# MCU.net
KiCad netlist of a schematic drawn in Altium Designer
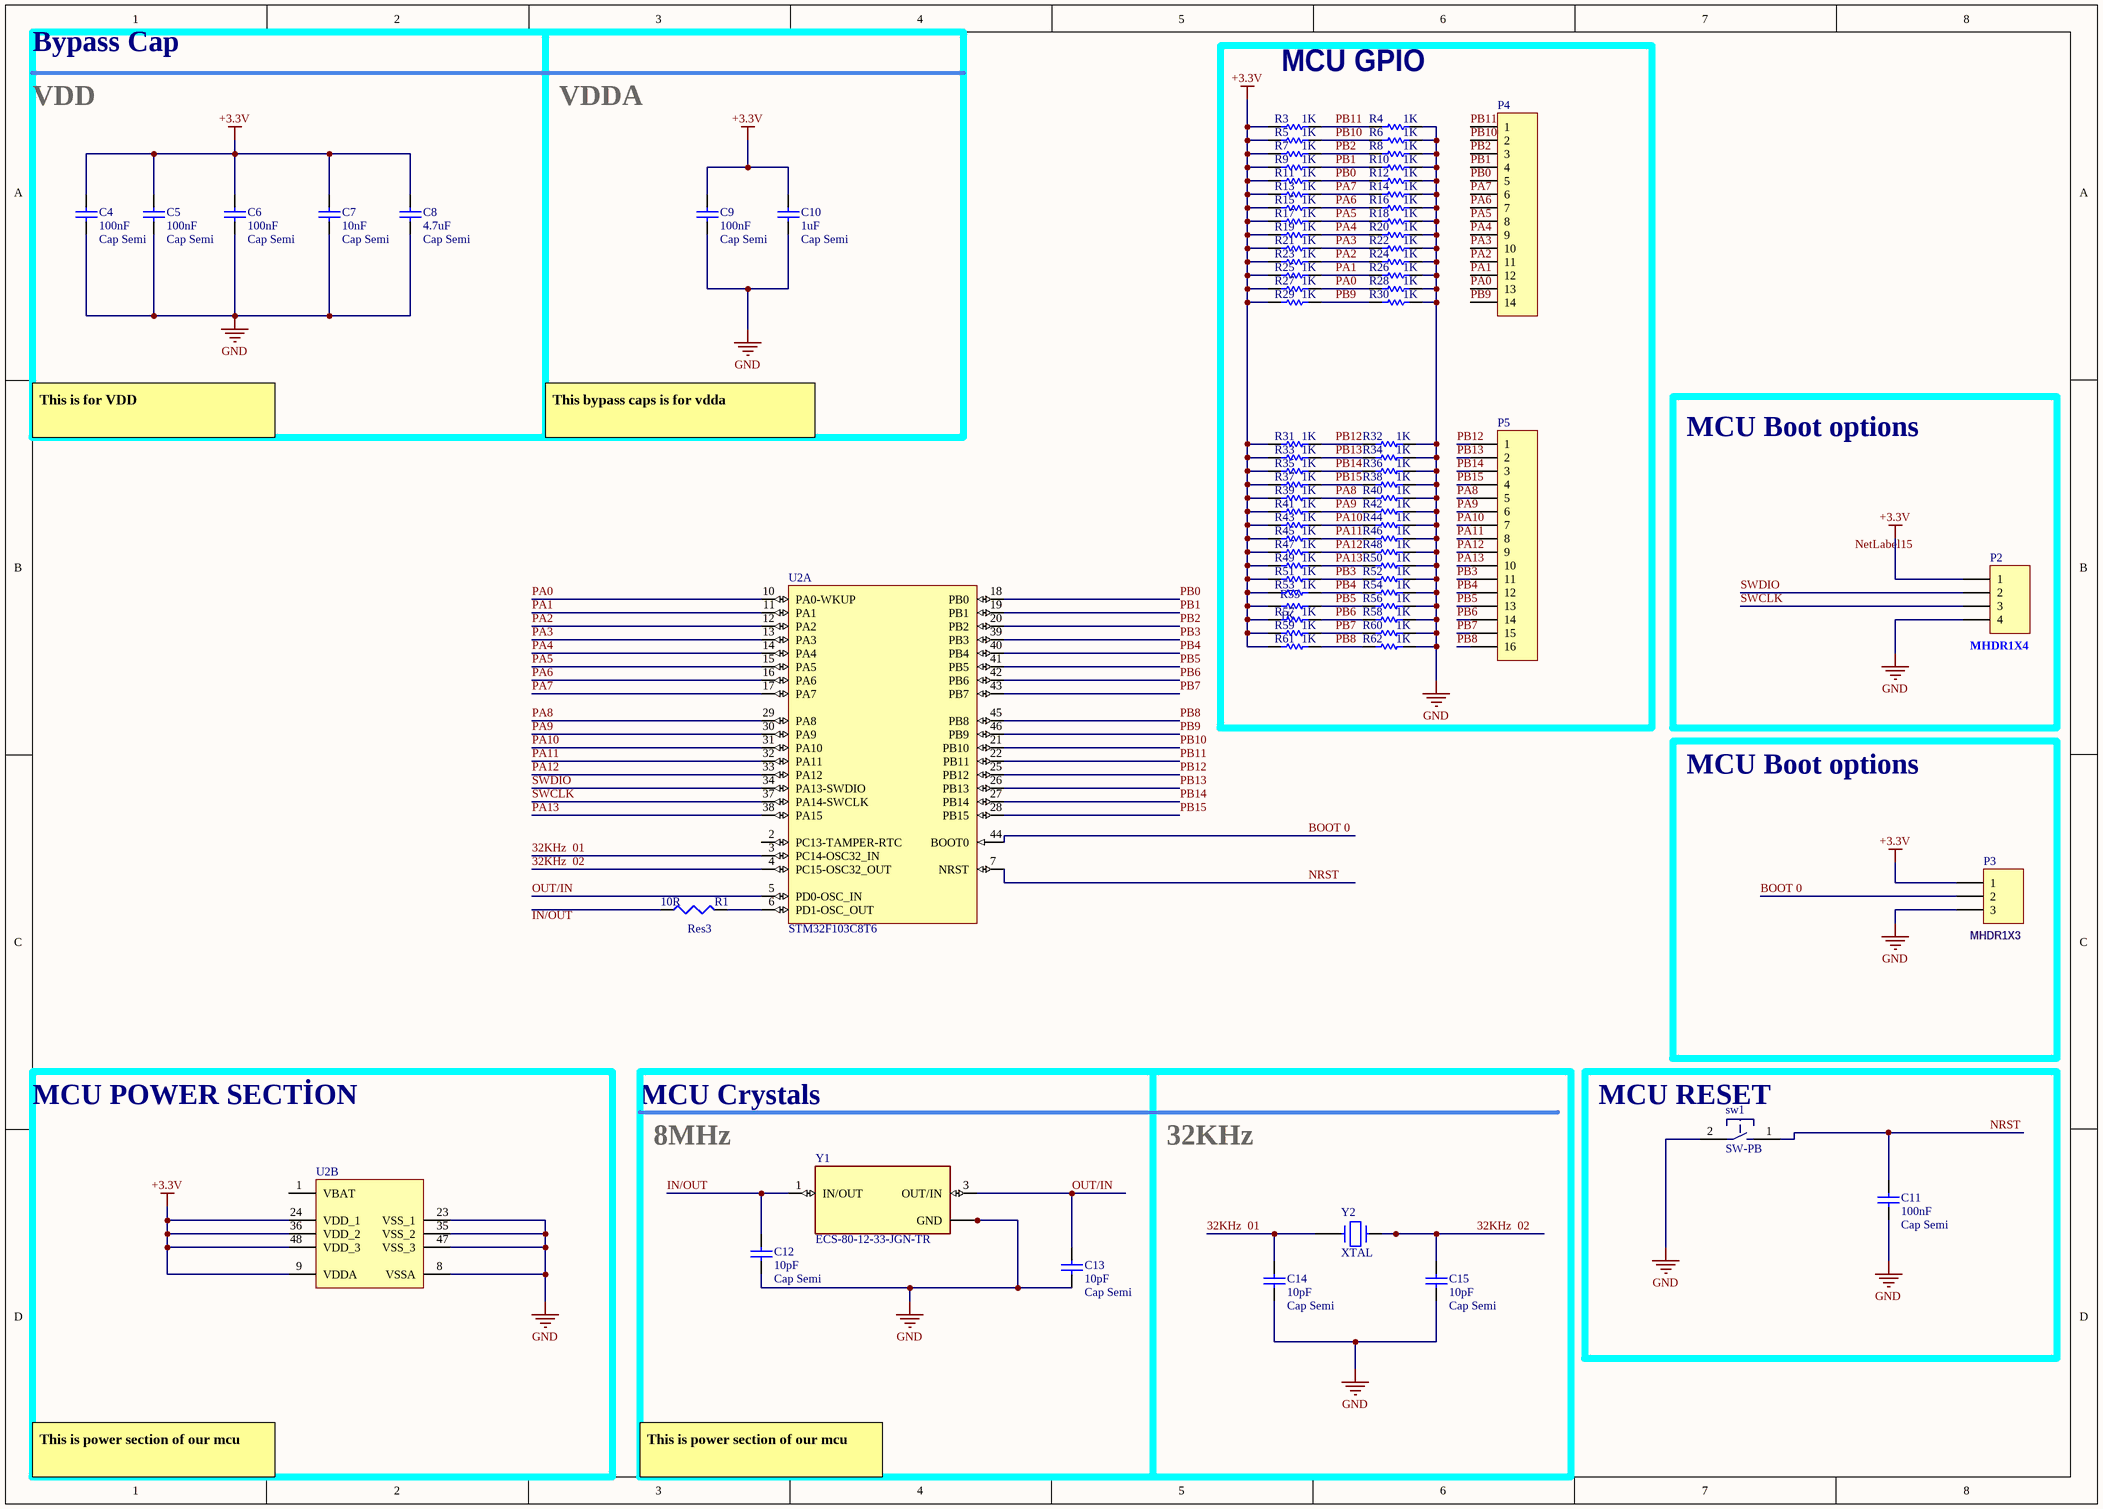
[diagram p0: MCU.SchDoc]

(export (version "E")
  (design (tool "Eeschema 10.0.6"))
  (components
    (comp (ref "C4")
      (value "Cap Semi")
      (footprint "1608[0603]")
      (description "Capacitor (Semiconductor SIM Model)")
      (fields (field (name "ALTIUM_VALUE") "100nF") (field (name "PUBLISHER") "Altium Limited"))
      (libsource (lib "Miscellaneous Devices") (part "Cap Semi"))
    )
    (comp (ref "C5")
      (value "Cap Semi")
      (footprint "1608[0603]")
      (description "Capacitor (Semiconductor SIM Model)")
      (fields (field (name "ALTIUM_VALUE") "100nF") (field (name "PUBLISHER") "Altium Limited"))
      (libsource (lib "Miscellaneous Devices") (part "Cap Semi"))
    )
    (comp (ref "C6")
      (value "Cap Semi")
      (footprint "1608[0603]")
      (description "Capacitor (Semiconductor SIM Model)")
      (fields (field (name "ALTIUM_VALUE") "100nF") (field (name "PUBLISHER") "Altium Limited"))
      (libsource (lib "Miscellaneous Devices") (part "Cap Semi"))
    )
    (comp (ref "C7")
      (value "Cap Semi")
      (footprint "1608[0603]")
      (description "Capacitor (Semiconductor SIM Model)")
      (fields (field (name "ALTIUM_VALUE") "10nF") (field (name "PUBLISHER") "Altium Limited"))
      (libsource (lib "Miscellaneous Devices") (part "Cap Semi"))
    )
    (comp (ref "C8")
      (value "Cap Semi")
      (footprint "1608[0603]")
      (description "Capacitor (Semiconductor SIM Model)")
      (fields (field (name "ALTIUM_VALUE") "4.7uF") (field (name "PUBLISHER") "Altium Limited"))
      (libsource (lib "Miscellaneous Devices") (part "Cap Semi"))
    )
    (comp (ref "C9")
      (value "Cap Semi")
      (footprint "1608[0603]")
      (description "Capacitor (Semiconductor SIM Model)")
      (fields (field (name "ALTIUM_VALUE") "100nF") (field (name "PUBLISHER") "Altium Limited"))
      (libsource (lib "Miscellaneous Devices") (part "Cap Semi"))
    )
    (comp (ref "C10")
      (value "Cap Semi")
      (footprint "1608[0603]")
      (description "Capacitor (Semiconductor SIM Model)")
      (fields (field (name "ALTIUM_VALUE") "1uF") (field (name "PUBLISHER") "Altium Limited"))
      (libsource (lib "Miscellaneous Devices") (part "Cap Semi"))
    )
    (comp (ref "C11")
      (value "Cap Semi")
      (footprint "1608[0603]")
      (description "Capacitor (Semiconductor SIM Model)")
      (fields (field (name "ALTIUM_VALUE") "100nF") (field (name "PUBLISHER") "Altium Limited"))
      (libsource (lib "Miscellaneous Devices") (part "Cap Semi"))
    )
    (comp (ref "C12")
      (value "Cap Semi")
      (footprint "0402")
      (description "Capacitor (Semiconductor SIM Model)")
      (fields (field (name "ALTIUM_VALUE") "10pF") (field (name "PUBLISHER") "Altium Limited"))
      (libsource (lib "Miscellaneous Devices") (part "Cap Semi"))
    )
    (comp (ref "C13")
      (value "Cap Semi")
      (footprint "0402")
      (description "Capacitor (Semiconductor SIM Model)")
      (fields (field (name "ALTIUM_VALUE") "10pF") (field (name "PUBLISHER") "Altium Limited"))
      (libsource (lib "Miscellaneous Devices") (part "Cap Semi"))
    )
    (comp (ref "C14")
      (value "Cap Semi")
      (footprint "0402")
      (description "Capacitor (Semiconductor SIM Model)")
      (fields (field (name "ALTIUM_VALUE") "10pF") (field (name "PUBLISHER") "Altium Limited"))
      (libsource (lib "Miscellaneous Devices") (part "Cap Semi"))
    )
    (comp (ref "C15")
      (value "Cap Semi")
      (footprint "0402")
      (description "Capacitor (Semiconductor SIM Model)")
      (fields (field (name "ALTIUM_VALUE") "10pF") (field (name "PUBLISHER") "Altium Limited"))
      (libsource (lib "Miscellaneous Devices") (part "Cap Semi"))
    )
    (comp (ref "P2")
      (value "Header 4")
      (footprint "MY_MA04-1W")
      (description "Header, 4-Pin")
      (fields (field (name "ASID PART NUMBER") "Header 4-AS"))
      (libsource (lib "Mylib+Rev+4") (part "Header 4"))
    )
    (comp (ref "P3")
      (value "Header 3")
      (footprint "MY_MA03-1W")
      (description "Header, 3-Pin")
      (fields (field (name "ASID PART NUMBER") "Header 3-AS"))
      (libsource (lib "Mylib+Rev+4") (part "Header 3"))
    )
    (comp (ref "P4")
      (value "Header 14")
      (footprint "MY_FE14")
      (description "Header, 14-Pin")
      (fields (field (name "ASID PART NUMBER") "Header 14-AS"))
      (libsource (lib "Mylib+Rev+4") (part "Header 14"))
    )
    (comp (ref "P5")
      (value "Header 16")
      (footprint "MY_FE16")
      (description "Header, 16-Pin")
      (fields (field (name "ASID PART NUMBER") "Header 16-AS"))
      (libsource (lib "Mylib+Rev+4") (part "Header 16"))
    )
    (comp (ref "R1")
      (value "Res3")
      (footprint "J1-0603")
      (description "Resistor")
      (fields (field (name "ALTIUM_VALUE") "10R") (field (name "PUBLISHER") "Altium Limited"))
      (libsource (lib "Miscellaneous Devices") (part "Res3"))
    )
    (comp (ref "R3")
      (value "1K")
      (footprint "MY_0603")
      (description "Standard resistor")
      (fields (field (name "ASID PART NUMBER") "Res-AS"))
      (libsource (lib "Mylib+Rev+4") (part "Res"))
    )
    (comp (ref "R4")
      (value "1K")
      (footprint "MY_0603")
      (description "Standard resistor")
      (fields (field (name "ASID PART NUMBER") "Res-AS"))
      (libsource (lib "Mylib+Rev+4") (part "Res"))
    )
    (comp (ref "R5")
      (value "1K")
      (footprint "MY_0603")
      (description "Standard resistor")
      (fields (field (name "ASID PART NUMBER") "Res-AS"))
      (libsource (lib "Mylib+Rev+4") (part "Res"))
    )
    (comp (ref "R6")
      (value "1K")
      (footprint "MY_0603")
      (description "Standard resistor")
      (fields (field (name "ASID PART NUMBER") "Res-AS"))
      (libsource (lib "Mylib+Rev+4") (part "Res"))
    )
    (comp (ref "R7")
      (value "1K")
      (footprint "MY_0603")
      (description "Standard resistor")
      (fields (field (name "ASID PART NUMBER") "Res-AS"))
      (libsource (lib "Mylib+Rev+4") (part "Res"))
    )
    (comp (ref "R8")
      (value "1K")
      (footprint "MY_0603")
      (description "Standard resistor")
      (fields (field (name "ASID PART NUMBER") "Res-AS"))
      (libsource (lib "Mylib+Rev+4") (part "Res"))
    )
    (comp (ref "R9")
      (value "1K")
      (footprint "MY_0603")
      (description "Standard resistor")
      (fields (field (name "ASID PART NUMBER") "Res-AS"))
      (libsource (lib "Mylib+Rev+4") (part "Res"))
    )
    (comp (ref "R10")
      (value "1K")
      (footprint "MY_0603")
      (description "Standard resistor")
      (fields (field (name "ASID PART NUMBER") "Res-AS"))
      (libsource (lib "Mylib+Rev+4") (part "Res"))
    )
    (comp (ref "R11")
      (value "1K")
      (footprint "MY_0603")
      (description "Standard resistor")
      (fields (field (name "ASID PART NUMBER") "Res-AS"))
      (libsource (lib "Mylib+Rev+4") (part "Res"))
    )
    (comp (ref "R12")
      (value "1K")
      (footprint "MY_0603")
      (description "Standard resistor")
      (fields (field (name "ASID PART NUMBER") "Res-AS"))
      (libsource (lib "Mylib+Rev+4") (part "Res"))
    )
    (comp (ref "R13")
      (value "1K")
      (footprint "MY_0603")
      (description "Standard resistor")
      (fields (field (name "ASID PART NUMBER") "Res-AS"))
      (libsource (lib "Mylib+Rev+4") (part "Res"))
    )
    (comp (ref "R14")
      (value "1K")
      (footprint "MY_0603")
      (description "Standard resistor")
      (fields (field (name "ASID PART NUMBER") "Res-AS"))
      (libsource (lib "Mylib+Rev+4") (part "Res"))
    )
    (comp (ref "R15")
      (value "1K")
      (footprint "MY_0603")
      (description "Standard resistor")
      (fields (field (name "ASID PART NUMBER") "Res-AS"))
      (libsource (lib "Mylib+Rev+4") (part "Res"))
    )
    (comp (ref "R16")
      (value "1K")
      (footprint "MY_0603")
      (description "Standard resistor")
      (fields (field (name "ASID PART NUMBER") "Res-AS"))
      (libsource (lib "Mylib+Rev+4") (part "Res"))
    )
    (comp (ref "R17")
      (value "1K")
      (footprint "MY_0603")
      (description "Standard resistor")
      (fields (field (name "ASID PART NUMBER") "Res-AS"))
      (libsource (lib "Mylib+Rev+4") (part "Res"))
    )
    (comp (ref "R18")
      (value "1K")
      (footprint "MY_0603")
      (description "Standard resistor")
      (fields (field (name "ASID PART NUMBER") "Res-AS"))
      (libsource (lib "Mylib+Rev+4") (part "Res"))
    )
    (comp (ref "R19")
      (value "1K")
      (footprint "MY_0603")
      (description "Standard resistor")
      (fields (field (name "ASID PART NUMBER") "Res-AS"))
      (libsource (lib "Mylib+Rev+4") (part "Res"))
    )
    (comp (ref "R20")
      (value "1K")
      (footprint "MY_0603")
      (description "Standard resistor")
      (fields (field (name "ASID PART NUMBER") "Res-AS"))
      (libsource (lib "Mylib+Rev+4") (part "Res"))
    )
    (comp (ref "R21")
      (value "1K")
      (footprint "MY_0603")
      (description "Standard resistor")
      (fields (field (name "ASID PART NUMBER") "Res-AS"))
      (libsource (lib "Mylib+Rev+4") (part "Res"))
    )
    (comp (ref "R22")
      (value "1K")
      (footprint "MY_0603")
      (description "Standard resistor")
      (fields (field (name "ASID PART NUMBER") "Res-AS"))
      (libsource (lib "Mylib+Rev+4") (part "Res"))
    )
    (comp (ref "R23")
      (value "1K")
      (footprint "MY_0603")
      (description "Standard resistor")
      (fields (field (name "ASID PART NUMBER") "Res-AS"))
      (libsource (lib "Mylib+Rev+4") (part "Res"))
    )
    (comp (ref "R24")
      (value "1K")
      (footprint "MY_0603")
      (description "Standard resistor")
      (fields (field (name "ASID PART NUMBER") "Res-AS"))
      (libsource (lib "Mylib+Rev+4") (part "Res"))
    )
    (comp (ref "R25")
      (value "1K")
      (footprint "MY_0603")
      (description "Standard resistor")
      (fields (field (name "ASID PART NUMBER") "Res-AS"))
      (libsource (lib "Mylib+Rev+4") (part "Res"))
    )
    (comp (ref "R26")
      (value "1K")
      (footprint "MY_0603")
      (description "Standard resistor")
      (fields (field (name "ASID PART NUMBER") "Res-AS"))
      (libsource (lib "Mylib+Rev+4") (part "Res"))
    )
    (comp (ref "R27")
      (value "1K")
      (footprint "MY_0603")
      (description "Standard resistor")
      (fields (field (name "ASID PART NUMBER") "Res-AS"))
      (libsource (lib "Mylib+Rev+4") (part "Res"))
    )
    (comp (ref "R28")
      (value "1K")
      (footprint "MY_0603")
      (description "Standard resistor")
      (fields (field (name "ASID PART NUMBER") "Res-AS"))
      (libsource (lib "Mylib+Rev+4") (part "Res"))
    )
    (comp (ref "R29")
      (value "1K")
      (footprint "MY_0603")
      (description "Standard resistor")
      (fields (field (name "ASID PART NUMBER") "Res-AS"))
      (libsource (lib "Mylib+Rev+4") (part "Res"))
    )
    (comp (ref "R30")
      (value "1K")
      (footprint "MY_0603")
      (description "Standard resistor")
      (fields (field (name "ASID PART NUMBER") "Res-AS"))
      (libsource (lib "Mylib+Rev+4") (part "Res"))
    )
    (comp (ref "R31")
      (value "1K")
      (footprint "MY_0603")
      (description "Standard resistor")
      (fields (field (name "ASID PART NUMBER") "Res-AS"))
      (libsource (lib "Mylib+Rev+4") (part "Res"))
    )
    (comp (ref "R32")
      (value "1K")
      (footprint "MY_0603")
      (description "Standard resistor")
      (fields (field (name "ASID PART NUMBER") "Res-AS"))
      (libsource (lib "Mylib+Rev+4") (part "Res"))
    )
    (comp (ref "R33")
      (value "1K")
      (footprint "MY_0603")
      (description "Standard resistor")
      (fields (field (name "ASID PART NUMBER") "Res-AS"))
      (libsource (lib "Mylib+Rev+4") (part "Res"))
    )
    (comp (ref "R34")
      (value "1K")
      (footprint "MY_0603")
      (description "Standard resistor")
      (fields (field (name "ASID PART NUMBER") "Res-AS"))
      (libsource (lib "Mylib+Rev+4") (part "Res"))
    )
    (comp (ref "R35")
      (value "1K")
      (footprint "MY_0603")
      (description "Standard resistor")
      (fields (field (name "ASID PART NUMBER") "Res-AS"))
      (libsource (lib "Mylib+Rev+4") (part "Res"))
    )
    (comp (ref "R36")
      (value "1K")
      (footprint "MY_0603")
      (description "Standard resistor")
      (fields (field (name "ASID PART NUMBER") "Res-AS"))
      (libsource (lib "Mylib+Rev+4") (part "Res"))
    )
    (comp (ref "R37")
      (value "1K")
      (footprint "MY_0603")
      (description "Standard resistor")
      (fields (field (name "ASID PART NUMBER") "Res-AS"))
      (libsource (lib "Mylib+Rev+4") (part "Res"))
    )
    (comp (ref "R38")
      (value "1K")
      (footprint "MY_0603")
      (description "Standard resistor")
      (fields (field (name "ASID PART NUMBER") "Res-AS"))
      (libsource (lib "Mylib+Rev+4") (part "Res"))
    )
    (comp (ref "R39")
      (value "1K")
      (footprint "MY_0603")
      (description "Standard resistor")
      (fields (field (name "ASID PART NUMBER") "Res-AS"))
      (libsource (lib "Mylib+Rev+4") (part "Res"))
    )
    (comp (ref "R40")
      (value "1K")
      (footprint "MY_0603")
      (description "Standard resistor")
      (fields (field (name "ASID PART NUMBER") "Res-AS"))
      (libsource (lib "Mylib+Rev+4") (part "Res"))
    )
    (comp (ref "R41")
      (value "1K")
      (footprint "MY_0603")
      (description "Standard resistor")
      (fields (field (name "ASID PART NUMBER") "Res-AS"))
      (libsource (lib "Mylib+Rev+4") (part "Res"))
    )
    (comp (ref "R42")
      (value "1K")
      (footprint "MY_0603")
      (description "Standard resistor")
      (fields (field (name "ASID PART NUMBER") "Res-AS"))
      (libsource (lib "Mylib+Rev+4") (part "Res"))
    )
    (comp (ref "R43")
      (value "1K")
      (footprint "MY_0603")
      (description "Standard resistor")
      (fields (field (name "ASID PART NUMBER") "Res-AS"))
      (libsource (lib "Mylib+Rev+4") (part "Res"))
    )
    (comp (ref "R44")
      (value "1K")
      (footprint "MY_0603")
      (description "Standard resistor")
      (fields (field (name "ASID PART NUMBER") "Res-AS"))
      (libsource (lib "Mylib+Rev+4") (part "Res"))
    )
    (comp (ref "R45")
      (value "1K")
      (footprint "MY_0603")
      (description "Standard resistor")
      (fields (field (name "ASID PART NUMBER") "Res-AS"))
      (libsource (lib "Mylib+Rev+4") (part "Res"))
    )
    (comp (ref "R46")
      (value "1K")
      (footprint "MY_0603")
      (description "Standard resistor")
      (fields (field (name "ASID PART NUMBER") "Res-AS"))
      (libsource (lib "Mylib+Rev+4") (part "Res"))
    )
    (comp (ref "R47")
      (value "1K")
      (footprint "MY_0603")
      (description "Standard resistor")
      (fields (field (name "ASID PART NUMBER") "Res-AS"))
      (libsource (lib "Mylib+Rev+4") (part "Res"))
    )
    (comp (ref "R48")
      (value "1K")
      (footprint "MY_0603")
      (description "Standard resistor")
      (fields (field (name "ASID PART NUMBER") "Res-AS"))
      (libsource (lib "Mylib+Rev+4") (part "Res"))
    )
    (comp (ref "R49")
      (value "1K")
      (footprint "MY_0603")
      (description "Standard resistor")
      (fields (field (name "ASID PART NUMBER") "Res-AS"))
      (libsource (lib "Mylib+Rev+4") (part "Res"))
    )
    (comp (ref "R50")
      (value "1K")
      (footprint "MY_0603")
      (description "Standard resistor")
      (fields (field (name "ASID PART NUMBER") "Res-AS"))
      (libsource (lib "Mylib+Rev+4") (part "Res"))
    )
    (comp (ref "R51")
      (value "1K")
      (footprint "MY_0603")
      (description "Standard resistor")
      (fields (field (name "ASID PART NUMBER") "Res-AS"))
      (libsource (lib "Mylib+Rev+4") (part "Res"))
    )
    (comp (ref "R52")
      (value "1K")
      (footprint "MY_0603")
      (description "Standard resistor")
      (fields (field (name "ASID PART NUMBER") "Res-AS"))
      (libsource (lib "Mylib+Rev+4") (part "Res"))
    )
    (comp (ref "R53")
      (value "1K")
      (footprint "MY_0603")
      (description "Standard resistor")
      (fields (field (name "ASID PART NUMBER") "Res-AS"))
      (libsource (lib "Mylib+Rev+4") (part "Res"))
    )
    (comp (ref "R54")
      (value "1K")
      (footprint "MY_0603")
      (description "Standard resistor")
      (fields (field (name "ASID PART NUMBER") "Res-AS"))
      (libsource (lib "Mylib+Rev+4") (part "Res"))
    )
    (comp (ref "R55")
      (value "1K")
      (footprint "MY_0603")
      (description "Standard resistor")
      (fields (field (name "ASID PART NUMBER") "Res-AS"))
      (libsource (lib "Mylib+Rev+4") (part "Res"))
    )
    (comp (ref "R56")
      (value "1K")
      (footprint "MY_0603")
      (description "Standard resistor")
      (fields (field (name "ASID PART NUMBER") "Res-AS"))
      (libsource (lib "Mylib+Rev+4") (part "Res"))
    )
    (comp (ref "R57")
      (value "1K")
      (footprint "MY_0603")
      (description "Standard resistor")
      (fields (field (name "ASID PART NUMBER") "Res-AS"))
      (libsource (lib "Mylib+Rev+4") (part "Res"))
    )
    (comp (ref "R58")
      (value "1K")
      (footprint "MY_0603")
      (description "Standard resistor")
      (fields (field (name "ASID PART NUMBER") "Res-AS"))
      (libsource (lib "Mylib+Rev+4") (part "Res"))
    )
    (comp (ref "R59")
      (value "1K")
      (footprint "MY_0603")
      (description "Standard resistor")
      (fields (field (name "ASID PART NUMBER") "Res-AS"))
      (libsource (lib "Mylib+Rev+4") (part "Res"))
    )
    (comp (ref "R60")
      (value "1K")
      (footprint "MY_0603")
      (description "Standard resistor")
      (fields (field (name "ASID PART NUMBER") "Res-AS"))
      (libsource (lib "Mylib+Rev+4") (part "Res"))
    )
    (comp (ref "R61")
      (value "1K")
      (footprint "MY_0603")
      (description "Standard resistor")
      (fields (field (name "ASID PART NUMBER") "Res-AS"))
      (libsource (lib "Mylib+Rev+4") (part "Res"))
    )
    (comp (ref "R62")
      (value "1K")
      (footprint "MY_0603")
      (description "Standard resistor")
      (fields (field (name "ASID PART NUMBER") "Res-AS"))
      (libsource (lib "Mylib+Rev+4") (part "Res"))
    )
    (comp (ref "sw1")
      (value "SW-PB")
      (footprint "MY_PB-SMD")
      (description "small tac switch")
      (fields (field (name "ASID PART NUMBER") "Tac switch-AS"))
      (libsource (lib "Mylib+Rev+4") (part "Tac switch"))
    )
    (comp (ref "U2")
      (value "STM32F103C8T6")
      (footprint "STM-LQFP48_N")
      (fields (field (name "PARTNUMBER") "STM32F103C8T6"))
      (libsource (lib "smartmcu") (part "STM32F103C8T6"))
    )
    (comp (ref "Y1")
      (value "ECS-80-12-33-JGN-TR")
      (footprint "XTAL_ECS-240-8-33-AGN-TR")
      (libsource (lib "Mylib+Rev+4") (part "ECS-80-12-33-JGN-TR"))
    )
    (comp (ref "Y2")
      (value "XTAL")
      (footprint "MY_RTC_Crystal")
      (description "Crystal")
      (fields (field (name "ASID PART NUMBER") "Crystal-AS"))
      (libsource (lib "Mylib+Rev+4") (part "CRYSTAL"))
    )
  )
  (nets
    (net (code "1") (name "+3.3V") (class "Default")
      (node (ref "C10") (pin "2") (pinfunction "2_2") (pintype "passive"))
      (node (ref "C4") (pin "2") (pinfunction "2_2") (pintype "passive"))
      (node (ref "C5") (pin "2") (pinfunction "2_2") (pintype "passive"))
      (node (ref "C6") (pin "2") (pinfunction "2_2") (pintype "passive"))
      (node (ref "C7") (pin "2") (pinfunction "2_2") (pintype "passive"))
      (node (ref "C8") (pin "2") (pinfunction "2_2") (pintype "passive"))
      (node (ref "C9") (pin "2") (pinfunction "2_2") (pintype "passive"))
      (node (ref "P2") (pin "1") (pinfunction "1_1") (pintype "passive"))
      (node (ref "P3") (pin "1") (pinfunction "1_1") (pintype "passive"))
      (node (ref "R11") (pin "1") (pinfunction "1_1") (pintype "passive"))
      (node (ref "R13") (pin "1") (pinfunction "1_1") (pintype "passive"))
      (node (ref "R15") (pin "1") (pinfunction "1_1") (pintype "passive"))
      (node (ref "R17") (pin "1") (pinfunction "1_1") (pintype "passive"))
      (node (ref "R19") (pin "1") (pinfunction "1_1") (pintype "passive"))
      (node (ref "R21") (pin "1") (pinfunction "1_1") (pintype "passive"))
      (node (ref "R23") (pin "1") (pinfunction "1_1") (pintype "passive"))
      (node (ref "R25") (pin "1") (pinfunction "1_1") (pintype "passive"))
      (node (ref "R27") (pin "1") (pinfunction "1_1") (pintype "passive"))
      (node (ref "R29") (pin "1") (pinfunction "1_1") (pintype "passive"))
      (node (ref "R3") (pin "1") (pinfunction "1_1") (pintype "passive"))
      (node (ref "R31") (pin "1") (pinfunction "1_1") (pintype "passive"))
      (node (ref "R33") (pin "1") (pinfunction "1_1") (pintype "passive"))
      (node (ref "R35") (pin "1") (pinfunction "1_1") (pintype "passive"))
      (node (ref "R37") (pin "1") (pinfunction "1_1") (pintype "passive"))
      (node (ref "R39") (pin "1") (pinfunction "1_1") (pintype "passive"))
      (node (ref "R41") (pin "1") (pinfunction "1_1") (pintype "passive"))
      (node (ref "R43") (pin "1") (pinfunction "1_1") (pintype "passive"))
      (node (ref "R45") (pin "1") (pinfunction "1_1") (pintype "passive"))
      (node (ref "R47") (pin "1") (pinfunction "1_1") (pintype "passive"))
      (node (ref "R49") (pin "1") (pinfunction "1_1") (pintype "passive"))
      (node (ref "R5") (pin "1") (pinfunction "1_1") (pintype "passive"))
      (node (ref "R51") (pin "1") (pinfunction "1_1") (pintype "passive"))
      (node (ref "R53") (pin "1") (pinfunction "1_1") (pintype "passive"))
      (node (ref "R55") (pin "1") (pinfunction "1_1") (pintype "passive"))
      (node (ref "R57") (pin "1") (pinfunction "1_1") (pintype "passive"))
      (node (ref "R59") (pin "1") (pinfunction "1_1") (pintype "passive"))
      (node (ref "R61") (pin "1") (pinfunction "1_1") (pintype "passive"))
      (node (ref "R7") (pin "1") (pinfunction "1_1") (pintype "passive"))
      (node (ref "R9") (pin "1") (pinfunction "1_1") (pintype "passive"))
      (node (ref "U2") (pin "24") (pinfunction "VDD_1_24") (pintype "power_in"))
      (node (ref "U2") (pin "36") (pinfunction "VDD_2_36") (pintype "power_in"))
      (node (ref "U2") (pin "48") (pinfunction "VDD_3_48") (pintype "power_in"))
      (node (ref "U2") (pin "9") (pinfunction "VDDA_9") (pintype "power_in"))
    )
    (net (code "2") (name "/32KHz  01") (class "Default")
      (node (ref "C14") (pin "2") (pinfunction "2_2") (pintype "passive"))
      (node (ref "U2") (pin "3") (pinfunction "PC14-OSC32_IN_3") (pintype "bidirectional"))
      (node (ref "Y2") (pin "1") (pinfunction "1_1") (pintype "passive"))
    )
    (net (code "3") (name "/32KHz  02") (class "Default")
      (node (ref "C15") (pin "2") (pinfunction "2_2") (pintype "passive"))
      (node (ref "U2") (pin "4") (pinfunction "PC15-OSC32_OUT_4") (pintype "bidirectional"))
      (node (ref "Y2") (pin "2") (pinfunction "2_2") (pintype "passive"))
    )
    (net (code "4") (name "/BOOT 0") (class "Default")
      (node (ref "P3") (pin "2") (pinfunction "2_2") (pintype "passive"))
      (node (ref "U2") (pin "44") (pinfunction "BOOT0_44") (pintype "input"))
    )
    (net (code "5") (name "/IN{slash}OUT") (class "Default")
      (node (ref "C12") (pin "2") (pinfunction "2_2") (pintype "passive"))
      (node (ref "Y1") (pin "1") (pinfunction "IN/OUT_1") (pintype "bidirectional"))
    )
    (net (code "6") (name "/NRST") (class "Default")
      (node (ref "C11") (pin "2") (pinfunction "2_2") (pintype "passive"))
      (node (ref "U2") (pin "7") (pinfunction "NRST_7") (pintype "bidirectional"))
      (node (ref "sw1") (pin "1") (pinfunction "1_1") (pintype "passive"))
    )
    (net (code "8") (name "/OUT{slash}IN") (class "Default")
      (node (ref "C13") (pin "2") (pinfunction "2_2") (pintype "passive"))
      (node (ref "U2") (pin "5") (pinfunction "PD0-OSC_IN_5") (pintype "bidirectional"))
      (node (ref "Y1") (pin "3") (pinfunction "OUT/IN_3") (pintype "bidirectional"))
    )
    (net (code "9") (name "/PA0") (class "Default")
      (node (ref "P4") (pin "13") (pinfunction "13_13") (pintype "passive"))
      (node (ref "R27") (pin "2") (pinfunction "2_2") (pintype "passive"))
      (node (ref "R28") (pin "1") (pinfunction "1_1") (pintype "passive"))
      (node (ref "U2") (pin "10") (pinfunction "PA0-WKUP_10") (pintype "bidirectional"))
    )
    (net (code "10") (name "/PA1") (class "Default")
      (node (ref "P4") (pin "12") (pinfunction "12_12") (pintype "passive"))
      (node (ref "R25") (pin "2") (pinfunction "2_2") (pintype "passive"))
      (node (ref "R26") (pin "1") (pinfunction "1_1") (pintype "passive"))
      (node (ref "U2") (pin "11") (pinfunction "PA1_11") (pintype "bidirectional"))
    )
    (net (code "11") (name "/PA2") (class "Default")
      (node (ref "P4") (pin "11") (pinfunction "11_11") (pintype "passive"))
      (node (ref "R23") (pin "2") (pinfunction "2_2") (pintype "passive"))
      (node (ref "R24") (pin "1") (pinfunction "1_1") (pintype "passive"))
      (node (ref "U2") (pin "12") (pinfunction "PA2_12") (pintype "bidirectional"))
    )
    (net (code "12") (name "/PA3") (class "Default")
      (node (ref "P4") (pin "10") (pinfunction "10_10") (pintype "passive"))
      (node (ref "R21") (pin "2") (pinfunction "2_2") (pintype "passive"))
      (node (ref "R22") (pin "1") (pinfunction "1_1") (pintype "passive"))
      (node (ref "U2") (pin "13") (pinfunction "PA3_13") (pintype "bidirectional"))
    )
    (net (code "13") (name "/PA4") (class "Default")
      (node (ref "P4") (pin "9") (pinfunction "9_9") (pintype "passive"))
      (node (ref "R19") (pin "2") (pinfunction "2_2") (pintype "passive"))
      (node (ref "R20") (pin "1") (pinfunction "1_1") (pintype "passive"))
      (node (ref "U2") (pin "14") (pinfunction "PA4_14") (pintype "bidirectional"))
    )
    (net (code "14") (name "/PA5") (class "Default")
      (node (ref "P4") (pin "8") (pinfunction "8_8") (pintype "passive"))
      (node (ref "R17") (pin "2") (pinfunction "2_2") (pintype "passive"))
      (node (ref "R18") (pin "1") (pinfunction "1_1") (pintype "passive"))
      (node (ref "U2") (pin "15") (pinfunction "PA5_15") (pintype "bidirectional"))
    )
    (net (code "15") (name "/PA6") (class "Default")
      (node (ref "P4") (pin "7") (pinfunction "7_7") (pintype "passive"))
      (node (ref "R15") (pin "2") (pinfunction "2_2") (pintype "passive"))
      (node (ref "R16") (pin "1") (pinfunction "1_1") (pintype "passive"))
      (node (ref "U2") (pin "16") (pinfunction "PA6_16") (pintype "bidirectional"))
    )
    (net (code "16") (name "/PA7") (class "Default")
      (node (ref "P4") (pin "6") (pinfunction "6_6") (pintype "passive"))
      (node (ref "R13") (pin "2") (pinfunction "2_2") (pintype "passive"))
      (node (ref "R14") (pin "1") (pinfunction "1_1") (pintype "passive"))
      (node (ref "U2") (pin "17") (pinfunction "PA7_17") (pintype "bidirectional"))
    )
    (net (code "17") (name "/PA8") (class "Default")
      (node (ref "P5") (pin "5") (pinfunction "5_5") (pintype "passive"))
      (node (ref "R39") (pin "2") (pinfunction "2_2") (pintype "passive"))
      (node (ref "R40") (pin "1") (pinfunction "1_1") (pintype "passive"))
      (node (ref "U2") (pin "29") (pinfunction "PA8_29") (pintype "bidirectional"))
    )
    (net (code "18") (name "/PA9") (class "Default")
      (node (ref "P5") (pin "6") (pinfunction "6_6") (pintype "passive"))
      (node (ref "R41") (pin "2") (pinfunction "2_2") (pintype "passive"))
      (node (ref "R42") (pin "1") (pinfunction "1_1") (pintype "passive"))
      (node (ref "U2") (pin "30") (pinfunction "PA9_30") (pintype "bidirectional"))
    )
    (net (code "19") (name "/PA10") (class "Default")
      (node (ref "P5") (pin "7") (pinfunction "7_7") (pintype "passive"))
      (node (ref "R43") (pin "2") (pinfunction "2_2") (pintype "passive"))
      (node (ref "R44") (pin "1") (pinfunction "1_1") (pintype "passive"))
      (node (ref "U2") (pin "31") (pinfunction "PA10_31") (pintype "bidirectional"))
    )
    (net (code "20") (name "/PA11") (class "Default")
      (node (ref "P5") (pin "8") (pinfunction "8_8") (pintype "passive"))
      (node (ref "R45") (pin "2") (pinfunction "2_2") (pintype "passive"))
      (node (ref "R46") (pin "1") (pinfunction "1_1") (pintype "passive"))
      (node (ref "U2") (pin "32") (pinfunction "PA11_32") (pintype "bidirectional"))
    )
    (net (code "21") (name "/PA12") (class "Default")
      (node (ref "P5") (pin "9") (pinfunction "9_9") (pintype "passive"))
      (node (ref "R47") (pin "2") (pinfunction "2_2") (pintype "passive"))
      (node (ref "R48") (pin "1") (pinfunction "1_1") (pintype "passive"))
      (node (ref "U2") (pin "33") (pinfunction "PA12_33") (pintype "bidirectional"))
    )
    (net (code "22") (name "/PA13") (class "Default")
      (node (ref "P5") (pin "10") (pinfunction "10_10") (pintype "passive"))
      (node (ref "R49") (pin "2") (pinfunction "2_2") (pintype "passive"))
      (node (ref "R50") (pin "1") (pinfunction "1_1") (pintype "passive"))
      (node (ref "U2") (pin "38") (pinfunction "PA15_38") (pintype "bidirectional"))
    )
    (net (code "23") (name "/PB0") (class "Default")
      (node (ref "P4") (pin "5") (pinfunction "5_5") (pintype "passive"))
      (node (ref "R11") (pin "2") (pinfunction "2_2") (pintype "passive"))
      (node (ref "R12") (pin "1") (pinfunction "1_1") (pintype "passive"))
      (node (ref "U2") (pin "18") (pinfunction "PB0_18") (pintype "bidirectional"))
    )
    (net (code "24") (name "/PB1") (class "Default")
      (node (ref "P4") (pin "4") (pinfunction "4_4") (pintype "passive"))
      (node (ref "R10") (pin "1") (pinfunction "1_1") (pintype "passive"))
      (node (ref "R9") (pin "2") (pinfunction "2_2") (pintype "passive"))
      (node (ref "U2") (pin "19") (pinfunction "PB1_19") (pintype "bidirectional"))
    )
    (net (code "25") (name "/PB2") (class "Default")
      (node (ref "P4") (pin "3") (pinfunction "3_3") (pintype "passive"))
      (node (ref "R7") (pin "2") (pinfunction "2_2") (pintype "passive"))
      (node (ref "R8") (pin "1") (pinfunction "1_1") (pintype "passive"))
      (node (ref "U2") (pin "20") (pinfunction "PB2_20") (pintype "bidirectional"))
    )
    (net (code "26") (name "/PB3") (class "Default")
      (node (ref "P5") (pin "11") (pinfunction "11_11") (pintype "passive"))
      (node (ref "R51") (pin "2") (pinfunction "2_2") (pintype "passive"))
      (node (ref "R52") (pin "1") (pinfunction "1_1") (pintype "passive"))
      (node (ref "U2") (pin "39") (pinfunction "PB3_39") (pintype "bidirectional"))
    )
    (net (code "27") (name "/PB4") (class "Default")
      (node (ref "P5") (pin "12") (pinfunction "12_12") (pintype "passive"))
      (node (ref "R53") (pin "2") (pinfunction "2_2") (pintype "passive"))
      (node (ref "R54") (pin "1") (pinfunction "1_1") (pintype "passive"))
      (node (ref "U2") (pin "40") (pinfunction "PB4_40") (pintype "bidirectional"))
    )
    (net (code "28") (name "/PB5") (class "Default")
      (node (ref "P5") (pin "13") (pinfunction "13_13") (pintype "passive"))
      (node (ref "R55") (pin "2") (pinfunction "2_2") (pintype "passive"))
      (node (ref "R56") (pin "1") (pinfunction "1_1") (pintype "passive"))
      (node (ref "U2") (pin "41") (pinfunction "PB5_41") (pintype "bidirectional"))
    )
    (net (code "29") (name "/PB6") (class "Default")
      (node (ref "P5") (pin "14") (pinfunction "14_14") (pintype "passive"))
      (node (ref "R57") (pin "2") (pinfunction "2_2") (pintype "passive"))
      (node (ref "R58") (pin "1") (pinfunction "1_1") (pintype "passive"))
      (node (ref "U2") (pin "42") (pinfunction "PB6_42") (pintype "bidirectional"))
    )
    (net (code "30") (name "/PB7") (class "Default")
      (node (ref "P5") (pin "15") (pinfunction "15_15") (pintype "passive"))
      (node (ref "R59") (pin "2") (pinfunction "2_2") (pintype "passive"))
      (node (ref "R60") (pin "1") (pinfunction "1_1") (pintype "passive"))
      (node (ref "U2") (pin "43") (pinfunction "PB7_43") (pintype "bidirectional"))
    )
    (net (code "31") (name "/PB8") (class "Default")
      (node (ref "P5") (pin "16") (pinfunction "16_16") (pintype "passive"))
      (node (ref "R61") (pin "2") (pinfunction "2_2") (pintype "passive"))
      (node (ref "R62") (pin "1") (pinfunction "1_1") (pintype "passive"))
      (node (ref "U2") (pin "45") (pinfunction "PB8_45") (pintype "bidirectional"))
    )
    (net (code "32") (name "/PB9") (class "Default")
      (node (ref "P4") (pin "14") (pinfunction "14_14") (pintype "passive"))
      (node (ref "R29") (pin "2") (pinfunction "2_2") (pintype "passive"))
      (node (ref "R30") (pin "1") (pinfunction "1_1") (pintype "passive"))
      (node (ref "U2") (pin "46") (pinfunction "PB9_46") (pintype "bidirectional"))
    )
    (net (code "33") (name "/PB10") (class "Default")
      (node (ref "P4") (pin "2") (pinfunction "2_2") (pintype "passive"))
      (node (ref "R5") (pin "2") (pinfunction "2_2") (pintype "passive"))
      (node (ref "R6") (pin "1") (pinfunction "1_1") (pintype "passive"))
      (node (ref "U2") (pin "21") (pinfunction "PB10_21") (pintype "bidirectional"))
    )
    (net (code "34") (name "/PB11") (class "Default")
      (node (ref "P4") (pin "1") (pinfunction "1_1") (pintype "passive"))
      (node (ref "R3") (pin "2") (pinfunction "2_2") (pintype "passive"))
      (node (ref "R4") (pin "1") (pinfunction "1_1") (pintype "passive"))
      (node (ref "U2") (pin "22") (pinfunction "PB11_22") (pintype "bidirectional"))
    )
    (net (code "35") (name "/PB12") (class "Default")
      (node (ref "P5") (pin "1") (pinfunction "1_1") (pintype "passive"))
      (node (ref "R31") (pin "2") (pinfunction "2_2") (pintype "passive"))
      (node (ref "R32") (pin "1") (pinfunction "1_1") (pintype "passive"))
      (node (ref "U2") (pin "25") (pinfunction "PB12_25") (pintype "bidirectional"))
    )
    (net (code "36") (name "/PB13") (class "Default")
      (node (ref "P5") (pin "2") (pinfunction "2_2") (pintype "passive"))
      (node (ref "R33") (pin "2") (pinfunction "2_2") (pintype "passive"))
      (node (ref "R34") (pin "1") (pinfunction "1_1") (pintype "passive"))
      (node (ref "U2") (pin "26") (pinfunction "PB13_26") (pintype "bidirectional"))
    )
    (net (code "37") (name "/PB14") (class "Default")
      (node (ref "P5") (pin "3") (pinfunction "3_3") (pintype "passive"))
      (node (ref "R35") (pin "2") (pinfunction "2_2") (pintype "passive"))
      (node (ref "R36") (pin "1") (pinfunction "1_1") (pintype "passive"))
      (node (ref "U2") (pin "27") (pinfunction "PB14_27") (pintype "bidirectional"))
    )
    (net (code "38") (name "/PB15") (class "Default")
      (node (ref "P5") (pin "4") (pinfunction "4_4") (pintype "passive"))
      (node (ref "R37") (pin "2") (pinfunction "2_2") (pintype "passive"))
      (node (ref "R38") (pin "1") (pinfunction "1_1") (pintype "passive"))
      (node (ref "U2") (pin "28") (pinfunction "PB15_28") (pintype "bidirectional"))
    )
    (net (code "39") (name "/SWCLK") (class "Default")
      (node (ref "P2") (pin "3") (pinfunction "3_3") (pintype "passive"))
      (node (ref "U2") (pin "37") (pinfunction "PA14-SWCLK_37") (pintype "bidirectional"))
    )
    (net (code "40") (name "/SWDIO") (class "Default")
      (node (ref "P2") (pin "2") (pinfunction "2_2") (pintype "passive"))
      (node (ref "U2") (pin "34") (pinfunction "PA13-SWDIO_34") (pintype "bidirectional"))
    )
    (net (code "41") (name "GND") (class "Default")
      (node (ref "C10") (pin "1") (pinfunction "1_1") (pintype "passive"))
      (node (ref "C11") (pin "1") (pinfunction "1_1") (pintype "passive"))
      (node (ref "C12") (pin "1") (pinfunction "1_1") (pintype "passive"))
      (node (ref "C13") (pin "1") (pinfunction "1_1") (pintype "passive"))
      (node (ref "C14") (pin "1") (pinfunction "1_1") (pintype "passive"))
      (node (ref "C15") (pin "1") (pinfunction "1_1") (pintype "passive"))
      (node (ref "C4") (pin "1") (pinfunction "1_1") (pintype "passive"))
      (node (ref "C5") (pin "1") (pinfunction "1_1") (pintype "passive"))
      (node (ref "C6") (pin "1") (pinfunction "1_1") (pintype "passive"))
      (node (ref "C7") (pin "1") (pinfunction "1_1") (pintype "passive"))
      (node (ref "C8") (pin "1") (pinfunction "1_1") (pintype "passive"))
      (node (ref "C9") (pin "1") (pinfunction "1_1") (pintype "passive"))
      (node (ref "P2") (pin "4") (pinfunction "4_4") (pintype "passive"))
      (node (ref "P3") (pin "3") (pinfunction "3_3") (pintype "passive"))
      (node (ref "R10") (pin "2") (pinfunction "2_2") (pintype "passive"))
      (node (ref "R12") (pin "2") (pinfunction "2_2") (pintype "passive"))
      (node (ref "R14") (pin "2") (pinfunction "2_2") (pintype "passive"))
      (node (ref "R16") (pin "2") (pinfunction "2_2") (pintype "passive"))
      (node (ref "R18") (pin "2") (pinfunction "2_2") (pintype "passive"))
      (node (ref "R20") (pin "2") (pinfunction "2_2") (pintype "passive"))
      (node (ref "R22") (pin "2") (pinfunction "2_2") (pintype "passive"))
      (node (ref "R24") (pin "2") (pinfunction "2_2") (pintype "passive"))
      (node (ref "R26") (pin "2") (pinfunction "2_2") (pintype "passive"))
      (node (ref "R28") (pin "2") (pinfunction "2_2") (pintype "passive"))
      (node (ref "R30") (pin "2") (pinfunction "2_2") (pintype "passive"))
      (node (ref "R32") (pin "2") (pinfunction "2_2") (pintype "passive"))
      (node (ref "R34") (pin "2") (pinfunction "2_2") (pintype "passive"))
      (node (ref "R36") (pin "2") (pinfunction "2_2") (pintype "passive"))
      (node (ref "R38") (pin "2") (pinfunction "2_2") (pintype "passive"))
      (node (ref "R4") (pin "2") (pinfunction "2_2") (pintype "passive"))
      (node (ref "R40") (pin "2") (pinfunction "2_2") (pintype "passive"))
      (node (ref "R42") (pin "2") (pinfunction "2_2") (pintype "passive"))
      (node (ref "R44") (pin "2") (pinfunction "2_2") (pintype "passive"))
      (node (ref "R46") (pin "2") (pinfunction "2_2") (pintype "passive"))
      (node (ref "R48") (pin "2") (pinfunction "2_2") (pintype "passive"))
      (node (ref "R50") (pin "2") (pinfunction "2_2") (pintype "passive"))
      (node (ref "R52") (pin "2") (pinfunction "2_2") (pintype "passive"))
      (node (ref "R54") (pin "2") (pinfunction "2_2") (pintype "passive"))
      (node (ref "R56") (pin "2") (pinfunction "2_2") (pintype "passive"))
      (node (ref "R58") (pin "2") (pinfunction "2_2") (pintype "passive"))
      (node (ref "R6") (pin "2") (pinfunction "2_2") (pintype "passive"))
      (node (ref "R60") (pin "2") (pinfunction "2_2") (pintype "passive"))
      (node (ref "R62") (pin "2") (pinfunction "2_2") (pintype "passive"))
      (node (ref "R8") (pin "2") (pinfunction "2_2") (pintype "passive"))
      (node (ref "U2") (pin "23") (pinfunction "VSS_1_23") (pintype "power_in"))
      (node (ref "U2") (pin "35") (pinfunction "VSS_2_35") (pintype "power_in"))
      (node (ref "U2") (pin "47") (pinfunction "VSS_3_47") (pintype "power_in"))
      (node (ref "U2") (pin "8") (pinfunction "VSSA_8") (pintype "power_in"))
      (node (ref "Y1") (pin "2") (pinfunction "GND_2") (pintype "power_in"))
      (node (ref "Y1") (pin "4") (pinfunction "GND_4") (pintype "power_in"))
      (node (ref "sw1") (pin "2") (pinfunction "2_2") (pintype "passive"))
    )
    (net (code "42") (name "Net-(U2A-PD1-OSC_OUT)") (class "Default")
      (node (ref "R1") (pin "2") (pinfunction "2_2") (pintype "passive"))
      (node (ref "U2") (pin "6") (pinfunction "PD1-OSC_OUT_6") (pintype "bidirectional"))
    )
    (net (code "43") (name "unconnected-(R1-Pad1)") (class "Default")
      (node (ref "R1") (pin "1") (pinfunction "1_1") (pintype "passive"))
    )
    (net (code "44") (name "unconnected-(U2A-PC13-TAMPER-RTC-Pad2)") (class "Default")
      (node (ref "U2") (pin "2") (pinfunction "PC13-TAMPER-RTC_2") (pintype "bidirectional"))
    )
    (net (code "45") (name "unconnected-(U2B-VBAT-Pad1)") (class "Default")
      (node (ref "U2") (pin "1") (pinfunction "VBAT_1") (pintype "power_in"))
    )
  )
)
